# RYDAPLink.net
KiCad netlist of a schematic drawn in EasyEDA Pro
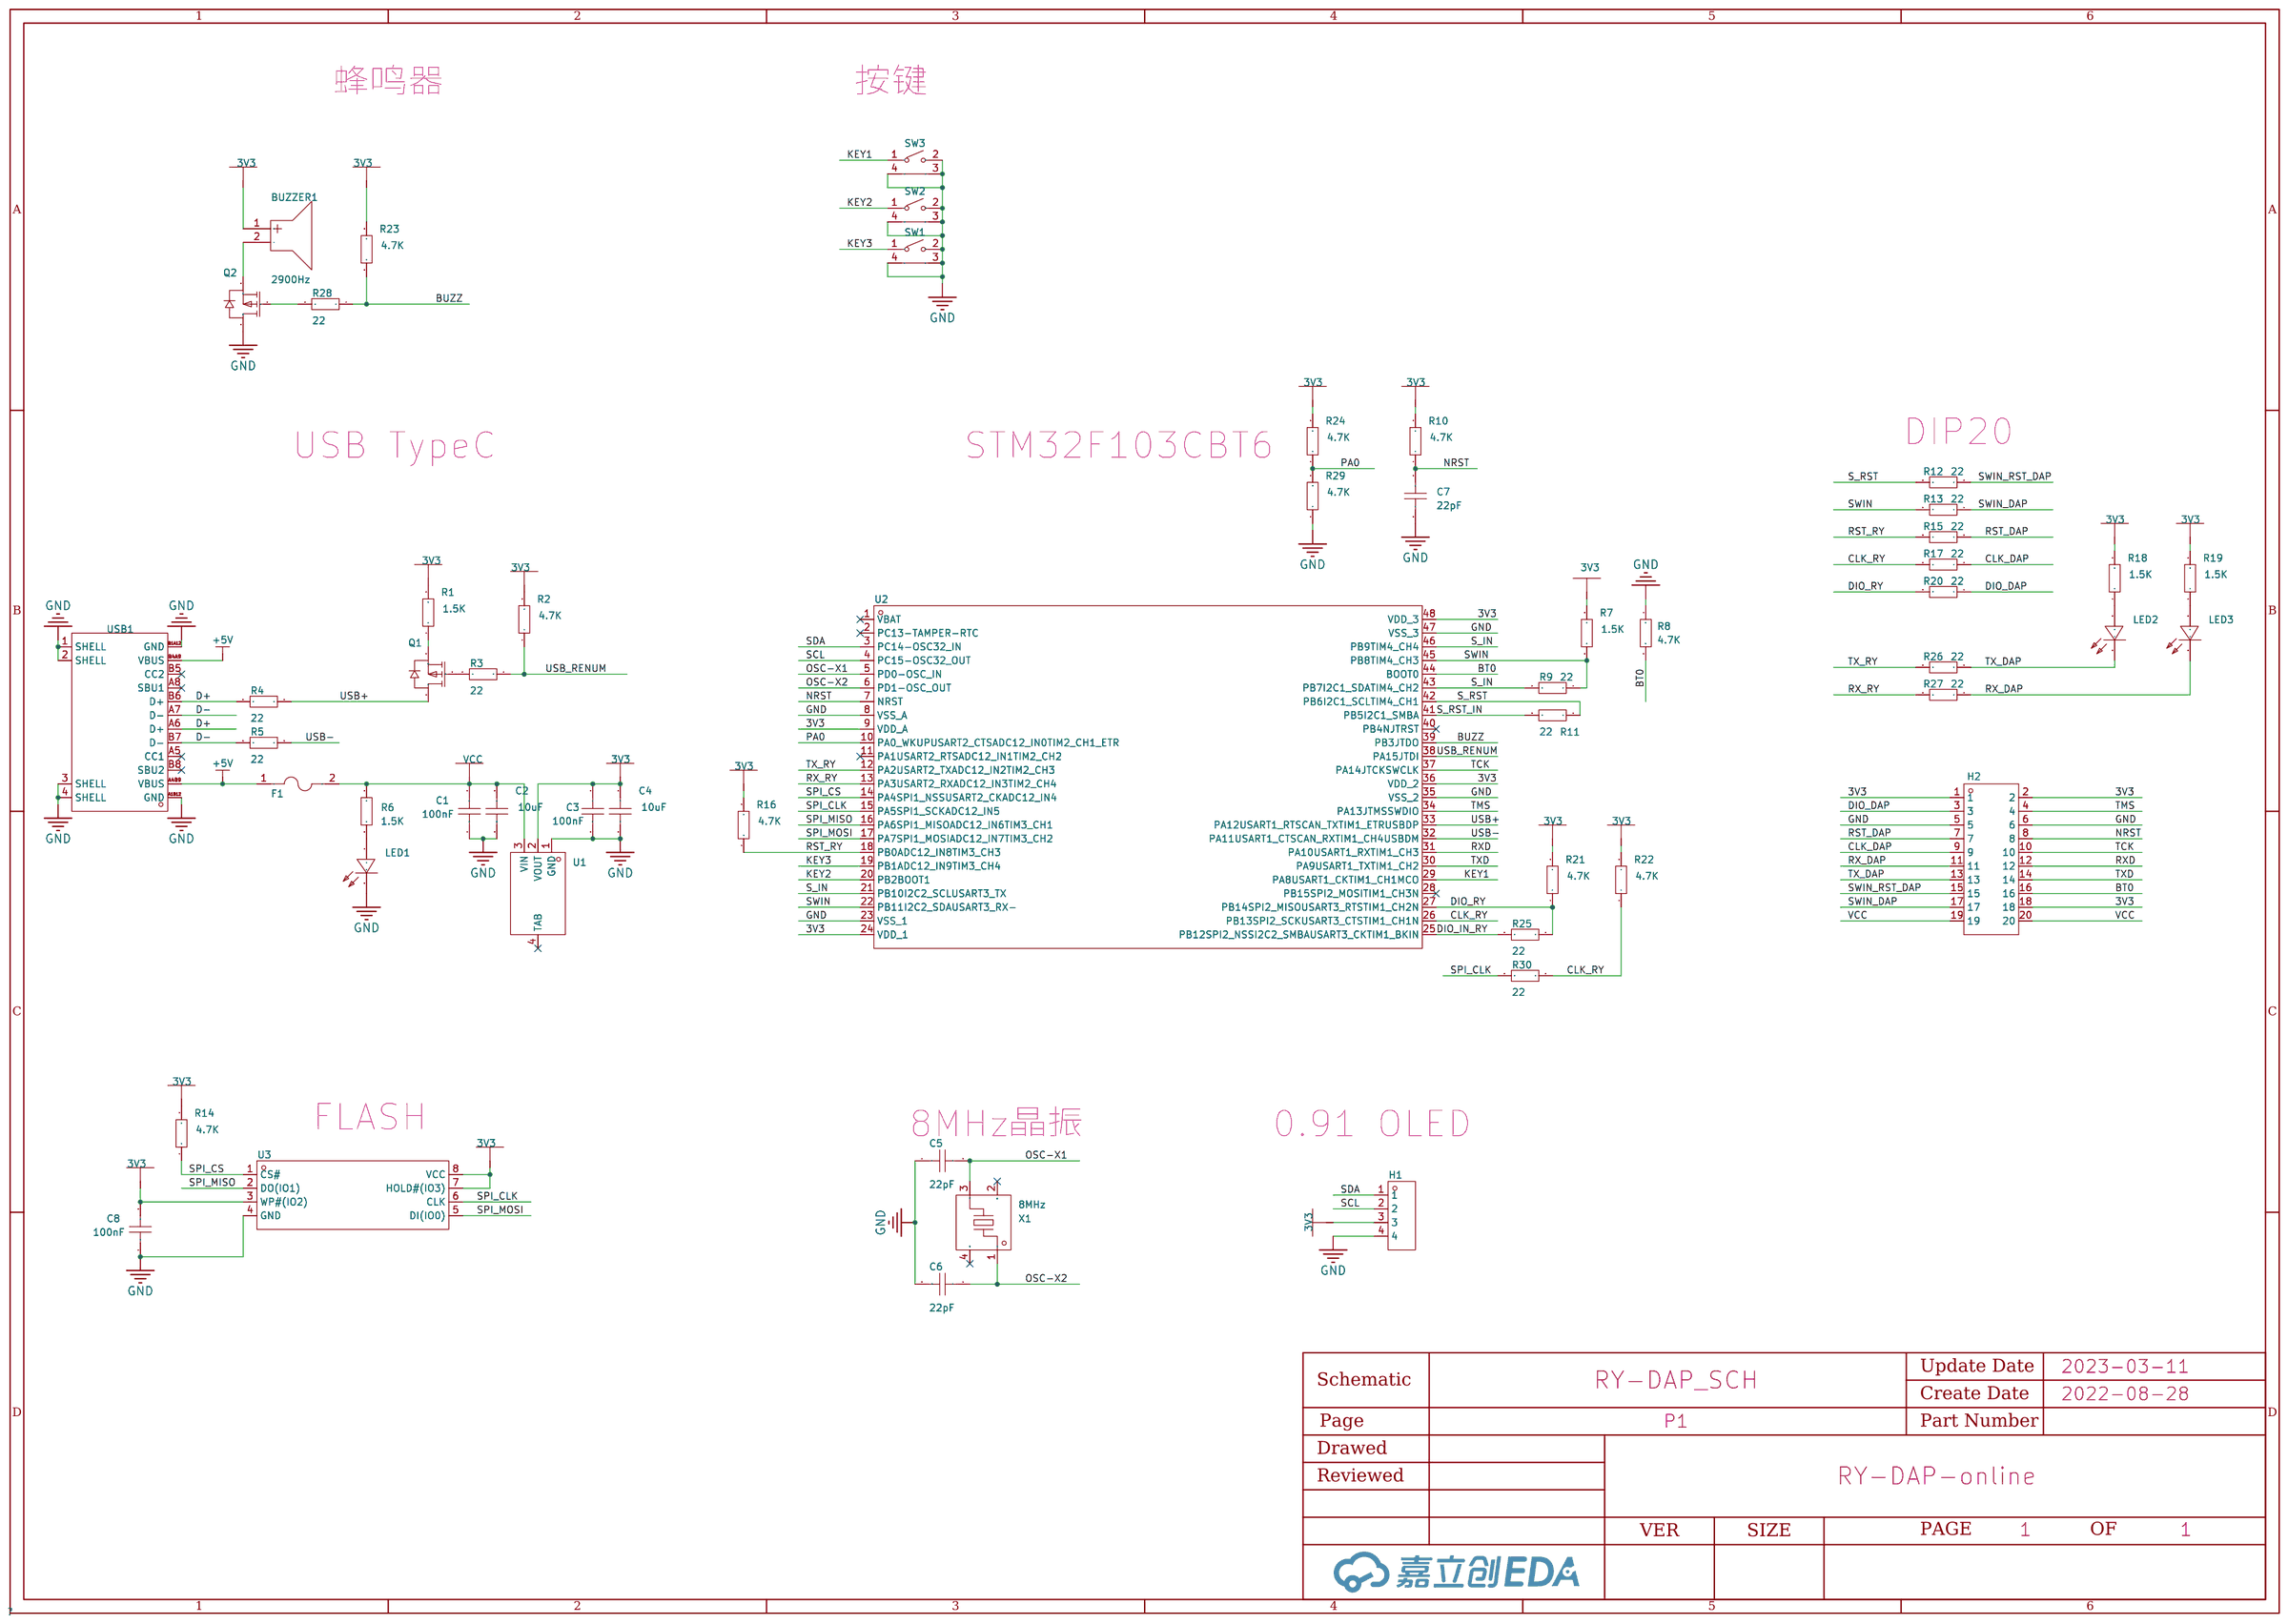
[diagram p0: schematic sheet]

(export (version "E")
  (design (tool "Eeschema 10.0.6"))
  (components
    (comp (ref "BUZZER1")
      (value "2900Hz")
      (footprint "easyedapro:BUZ-TH_BD9.6-P5.00-D0.7-FD")
      (description "驱动方式:有源(内含驱动线路);构造类型:电磁式;额定电压:3V;工作电压:2V~4V;频率:2900Hz;声压(SPL):85dB@3V,10cm;直径(φD):9.6mm;高度:5.2mm;")
      (fields (field (name "Manufacturer Part") "Cy-9650-3029") (field (name "Manufacturer") "CY(超音)"))
      (libsource (lib "easyedapro") (part "CY-9650-3029"))
    )
    (comp (ref "C1")
      (value "100nF")
      (footprint "easyedapro:C0603")
      (description "容值:100nF;精度:±10%;额定电压:50V;温度系数:X7R;")
      (fields
        (field (name "Manufacturer Part") "CC0603KRX7R9BB104")
        (field (name "Manufacturer") "YAGEO(国巨)")
      )
      (libsource (lib "easyedapro") (part "CC0603KRX7R9BB104"))
    )
    (comp (ref "C2")
      (value "10uF")
      (footprint "easyedapro:C0603")
      (description "容值:33pF;精度:±1%;额定电压:50V;温度系数:NP0;")
      (fields
        (field (name "Manufacturer Part") "CC0805FRNPO9BN330")
        (field (name "Manufacturer") "YAGEO(国巨)")
      )
      (libsource (lib "easyedapro") (part "CC0805FRNPO9BN330"))
    )
    (comp (ref "C3")
      (value "100nF")
      (footprint "easyedapro:C0603")
      (description "容值:100nF;精度:±10%;额定电压:50V;温度系数:X7R;")
      (fields
        (field (name "Manufacturer Part") "CC0603KRX7R9BB104")
        (field (name "Manufacturer") "YAGEO(国巨)")
      )
      (libsource (lib "easyedapro") (part "CC0603KRX7R9BB104"))
    )
    (comp (ref "C4")
      (value "10uF")
      (footprint "easyedapro:C0603")
      (description "容值:33pF;精度:±1%;额定电压:50V;温度系数:NP0;")
      (fields
        (field (name "Manufacturer Part") "CC0805FRNPO9BN330")
        (field (name "Manufacturer") "YAGEO(国巨)")
      )
      (libsource (lib "easyedapro") (part "CC0805FRNPO9BN330"))
    )
    (comp (ref "C5")
      (value "22pF")
      (footprint "easyedapro:C0603")
      (description "容值:33pF;精度:±1%;额定电压:50V;温度系数:NP0;")
      (fields
        (field (name "Manufacturer Part") "CC0805FRNPO9BN330")
        (field (name "Manufacturer") "YAGEO(国巨)")
      )
      (libsource (lib "easyedapro") (part "CC0805FRNPO9BN330"))
    )
    (comp (ref "C6")
      (value "22pF")
      (footprint "easyedapro:C0603")
      (description "容值:33pF;精度:±1%;额定电压:50V;温度系数:NP0;")
      (fields
        (field (name "Manufacturer Part") "CC0805FRNPO9BN330")
        (field (name "Manufacturer") "YAGEO(国巨)")
      )
      (libsource (lib "easyedapro") (part "CC0805FRNPO9BN330"))
    )
    (comp (ref "C7")
      (value "22pF")
      (footprint "easyedapro:C0603")
      (description "容值:33pF;精度:±1%;额定电压:50V;温度系数:NP0;")
      (fields
        (field (name "Manufacturer Part") "CC0805FRNPO9BN330")
        (field (name "Manufacturer") "YAGEO(国巨)")
      )
      (libsource (lib "easyedapro") (part "CC0805FRNPO9BN330"))
    )
    (comp (ref "C8")
      (value "100nF")
      (footprint "easyedapro:C0603")
      (description "容值:100nF;精度:±10%;额定电压:50V;温度系数:X7R;")
      (fields
        (field (name "Manufacturer Part") "CC0603KRX7R9BB104")
        (field (name "Manufacturer") "YAGEO(国巨)")
      )
      (libsource (lib "easyedapro") (part "CC0603KRX7R9BB104"))
    )
    (comp (ref "F1")
      (value "~")
      (footprint "easyedapro:F0805")
      (fields (field (name "Manufacturer Part") "ASMD0805-075") (field (name "Manufacturer") "JDTfuse集电通"))
      (libsource (lib "easyedapro") (part "ASMD0805-075"))
    )
    (comp (ref "H1")
      (value "~")
      (footprint "easyedapro:HDR-TH_4P-P2.54-V-M")
      (fields
        (field (name "Manufacturer Part") "KH-2.54PH180-1X4P-L11.5")
        (field (name "Manufacturer") "kinghelm(金航标)")
      )
      (libsource (lib "easyedapro") (part "KH-2.54PH180-1X4P-L11.5"))
    )
    (comp (ref "H2")
      (value "~")
      (footprint "easyedapro:HDR-TH_20P-P2.54-V-M-R2-C10-S2.54")
      (fields
        (field (name "Manufacturer Part") "1125-1210G0S120C002")
        (field (name "Manufacturer") "Wcon(维峰电子)")
      )
      (libsource (lib "easyedapro") (part "1125-1210G0S120C002"))
    )
    (comp (ref "LED1")
      (value "~")
      (footprint "easyedapro:LED0603-R-RD_RED")
      (description "尺寸1.6x0.8x0.8；IF=20ma：1.6~2.6v，620~640nm,51~150mcd金线，光强高，功耗低，可靠性好，寿命长")
      (fields (field (name "Manufacturer Part") "NCD0603R3") (field (name "Manufacturer") "国星光电"))
      (libsource (lib "easyedapro") (part "NCD0603R3"))
    )
    (comp (ref "LED2")
      (value "~")
      (footprint "easyedapro:LED0603-R-RD_RED")
      (description "尺寸1.6x0.8x0.8；IF=20ma：1.6~2.6v，620~640nm,51~150mcd金线，光强高，功耗低，可靠性好，寿命长")
      (fields (field (name "Manufacturer Part") "NCD0603R3") (field (name "Manufacturer") "国星光电"))
      (libsource (lib "easyedapro") (part "NCD0603R3"))
    )
    (comp (ref "LED3")
      (value "~")
      (footprint "easyedapro:LED0603-R-RD_RED")
      (description "尺寸1.6x0.8x0.8；IF=20ma：1.6~2.6v，620~640nm,51~150mcd金线，光强高，功耗低，可靠性好，寿命长")
      (fields (field (name "Manufacturer Part") "NCD0603R3") (field (name "Manufacturer") "国星光电"))
      (libsource (lib "easyedapro") (part "NCD0603R3"))
    )
    (comp (ref "Q1")
      (value "~")
      (footprint "easyedapro:SOT-23-3_L2.9-W1.4-P1.90-LS2.6-BR")
      (fields (field (name "Manufacturer Part") "AO3401") (field (name "Manufacturer") "TWGMC(台湾迪嘉)"))
      (libsource (lib "easyedapro") (part "AO3401_C727156"))
    )
    (comp (ref "Q2")
      (value "~")
      (footprint "easyedapro:SOT-23-3_L2.9-W1.4-P1.90-LS2.6-BR")
      (fields (field (name "Manufacturer Part") "AO3401") (field (name "Manufacturer") "TWGMC(台湾迪嘉)"))
      (libsource (lib "easyedapro") (part "AO3401_C727156"))
    )
    (comp (ref "R1")
      (value "1.5K")
      (footprint "easyedapro:R0603")
      (description "电阻类型:薄膜电阻;阻值:10kΩ;精度:±0.1%;功率:100mW;温度系数:±25ppm/;最大工作电压:75V;工作温度范围:-55~+155;")
      (fields
        (field (name "Manufacturer Part") "TR0603B10K0P0525Z")
        (field (name "Manufacturer") "EVER OHMS(天二科技)")
      )
      (libsource (lib "easyedapro") (part "R_0603_EU"))
    )
    (comp (ref "R2")
      (value "4.7K")
      (footprint "easyedapro:R0603")
      (description "电阻类型:薄膜电阻;阻值:10kΩ;精度:±0.1%;功率:100mW;温度系数:±25ppm/;最大工作电压:75V;工作温度范围:-55~+155;")
      (fields
        (field (name "Manufacturer Part") "TR0603B10K0P0525Z")
        (field (name "Manufacturer") "EVER OHMS(天二科技)")
      )
      (libsource (lib "easyedapro") (part "R_0603_EU"))
    )
    (comp (ref "R3")
      (value "22")
      (footprint "easyedapro:R0603")
      (description "电阻类型:薄膜电阻;阻值:10kΩ;精度:±0.1%;功率:100mW;温度系数:±25ppm/;最大工作电压:75V;工作温度范围:-55~+155;")
      (fields
        (field (name "Manufacturer Part") "TR0603B10K0P0525Z")
        (field (name "Manufacturer") "EVER OHMS(天二科技)")
      )
      (libsource (lib "easyedapro") (part "R_0603_EU"))
    )
    (comp (ref "R4")
      (value "22")
      (footprint "easyedapro:R0603")
      (description "电阻类型:薄膜电阻;阻值:10kΩ;精度:±0.1%;功率:100mW;温度系数:±25ppm/;最大工作电压:75V;工作温度范围:-55~+155;")
      (fields
        (field (name "Manufacturer Part") "TR0603B10K0P0525Z")
        (field (name "Manufacturer") "EVER OHMS(天二科技)")
      )
      (libsource (lib "easyedapro") (part "R_0603_EU"))
    )
    (comp (ref "R5")
      (value "22")
      (footprint "easyedapro:R0603")
      (description "电阻类型:薄膜电阻;阻值:10kΩ;精度:±0.1%;功率:100mW;温度系数:±25ppm/;最大工作电压:75V;工作温度范围:-55~+155;")
      (fields
        (field (name "Manufacturer Part") "TR0603B10K0P0525Z")
        (field (name "Manufacturer") "EVER OHMS(天二科技)")
      )
      (libsource (lib "easyedapro") (part "R_0603_EU"))
    )
    (comp (ref "R6")
      (value "1.5K")
      (footprint "easyedapro:R0603")
      (description "电阻类型:薄膜电阻;阻值:10kΩ;精度:±0.1%;功率:100mW;温度系数:±25ppm/;最大工作电压:75V;工作温度范围:-55~+155;")
      (fields
        (field (name "Manufacturer Part") "TR0603B10K0P0525Z")
        (field (name "Manufacturer") "EVER OHMS(天二科技)")
      )
      (libsource (lib "easyedapro") (part "R_0603_EU"))
    )
    (comp (ref "R7")
      (value "1.5K")
      (footprint "easyedapro:R0603")
      (description "电阻类型:薄膜电阻;阻值:10kΩ;精度:±0.1%;功率:100mW;温度系数:±25ppm/;最大工作电压:75V;工作温度范围:-55~+155;")
      (fields
        (field (name "Manufacturer Part") "TR0603B10K0P0525Z")
        (field (name "Manufacturer") "EVER OHMS(天二科技)")
      )
      (libsource (lib "easyedapro") (part "R_0603_EU"))
    )
    (comp (ref "R8")
      (value "4.7K")
      (footprint "easyedapro:R0603")
      (description "电阻类型:薄膜电阻;阻值:10kΩ;精度:±0.1%;功率:100mW;温度系数:±25ppm/;最大工作电压:75V;工作温度范围:-55~+155;")
      (fields
        (field (name "Manufacturer Part") "TR0603B10K0P0525Z")
        (field (name "Manufacturer") "EVER OHMS(天二科技)")
      )
      (libsource (lib "easyedapro") (part "R_0603_EU"))
    )
    (comp (ref "R9")
      (value "22")
      (footprint "easyedapro:R0603")
      (description "电阻类型:薄膜电阻;阻值:10kΩ;精度:±0.1%;功率:100mW;温度系数:±25ppm/;最大工作电压:75V;工作温度范围:-55~+155;")
      (fields
        (field (name "Manufacturer Part") "TR0603B10K0P0525Z")
        (field (name "Manufacturer") "EVER OHMS(天二科技)")
      )
      (libsource (lib "easyedapro") (part "R_0603_EU"))
    )
    (comp (ref "R10")
      (value "4.7K")
      (footprint "easyedapro:R0603")
      (description "电阻类型:薄膜电阻;阻值:10kΩ;精度:±0.1%;功率:100mW;温度系数:±25ppm/;最大工作电压:75V;工作温度范围:-55~+155;")
      (fields
        (field (name "Manufacturer Part") "TR0603B10K0P0525Z")
        (field (name "Manufacturer") "EVER OHMS(天二科技)")
      )
      (libsource (lib "easyedapro") (part "R_0603_EU"))
    )
    (comp (ref "R11")
      (value "22")
      (footprint "easyedapro:R0603")
      (description "电阻类型:薄膜电阻;阻值:10kΩ;精度:±0.1%;功率:100mW;温度系数:±25ppm/;最大工作电压:75V;工作温度范围:-55~+155;")
      (fields
        (field (name "Manufacturer Part") "TR0603B10K0P0525Z")
        (field (name "Manufacturer") "EVER OHMS(天二科技)")
      )
      (libsource (lib "easyedapro") (part "R_0603_EU"))
    )
    (comp (ref "R12")
      (value "22")
      (footprint "easyedapro:R0603")
      (description "电阻类型:薄膜电阻;阻值:10kΩ;精度:±0.1%;功率:100mW;温度系数:±25ppm/;最大工作电压:75V;工作温度范围:-55~+155;")
      (fields
        (field (name "Manufacturer Part") "TR0603B10K0P0525Z")
        (field (name "Manufacturer") "EVER OHMS(天二科技)")
      )
      (libsource (lib "easyedapro") (part "R_0603_EU"))
    )
    (comp (ref "R13")
      (value "22")
      (footprint "easyedapro:R0603")
      (description "电阻类型:薄膜电阻;阻值:10kΩ;精度:±0.1%;功率:100mW;温度系数:±25ppm/;最大工作电压:75V;工作温度范围:-55~+155;")
      (fields
        (field (name "Manufacturer Part") "TR0603B10K0P0525Z")
        (field (name "Manufacturer") "EVER OHMS(天二科技)")
      )
      (libsource (lib "easyedapro") (part "R_0603_EU"))
    )
    (comp (ref "R14")
      (value "4.7K")
      (footprint "easyedapro:R0603")
      (description "电阻类型:薄膜电阻;阻值:10kΩ;精度:±0.1%;功率:100mW;温度系数:±25ppm/;最大工作电压:75V;工作温度范围:-55~+155;")
      (fields
        (field (name "Manufacturer Part") "TR0603B10K0P0525Z")
        (field (name "Manufacturer") "EVER OHMS(天二科技)")
      )
      (libsource (lib "easyedapro") (part "R_0603_EU"))
    )
    (comp (ref "R15")
      (value "22")
      (footprint "easyedapro:R0603")
      (description "电阻类型:薄膜电阻;阻值:10kΩ;精度:±0.1%;功率:100mW;温度系数:±25ppm/;最大工作电压:75V;工作温度范围:-55~+155;")
      (fields
        (field (name "Manufacturer Part") "TR0603B10K0P0525Z")
        (field (name "Manufacturer") "EVER OHMS(天二科技)")
      )
      (libsource (lib "easyedapro") (part "R_0603_EU"))
    )
    (comp (ref "R16")
      (value "4.7K")
      (footprint "easyedapro:R0603")
      (description "电阻类型:薄膜电阻;阻值:10kΩ;精度:±0.1%;功率:100mW;温度系数:±25ppm/;最大工作电压:75V;工作温度范围:-55~+155;")
      (fields
        (field (name "Manufacturer Part") "TR0603B10K0P0525Z")
        (field (name "Manufacturer") "EVER OHMS(天二科技)")
      )
      (libsource (lib "easyedapro") (part "R_0603_EU"))
    )
    (comp (ref "R17")
      (value "22")
      (footprint "easyedapro:R0603")
      (description "电阻类型:薄膜电阻;阻值:10kΩ;精度:±0.1%;功率:100mW;温度系数:±25ppm/;最大工作电压:75V;工作温度范围:-55~+155;")
      (fields
        (field (name "Manufacturer Part") "TR0603B10K0P0525Z")
        (field (name "Manufacturer") "EVER OHMS(天二科技)")
      )
      (libsource (lib "easyedapro") (part "R_0603_EU"))
    )
    (comp (ref "R18")
      (value "1.5K")
      (footprint "easyedapro:R0603")
      (description "电阻类型:薄膜电阻;阻值:10kΩ;精度:±0.1%;功率:100mW;温度系数:±25ppm/;最大工作电压:75V;工作温度范围:-55~+155;")
      (fields
        (field (name "Manufacturer Part") "TR0603B10K0P0525Z")
        (field (name "Manufacturer") "EVER OHMS(天二科技)")
      )
      (libsource (lib "easyedapro") (part "R_0603_EU"))
    )
    (comp (ref "R19")
      (value "1.5K")
      (footprint "easyedapro:R0603")
      (description "电阻类型:薄膜电阻;阻值:10kΩ;精度:±0.1%;功率:100mW;温度系数:±25ppm/;最大工作电压:75V;工作温度范围:-55~+155;")
      (fields
        (field (name "Manufacturer Part") "TR0603B10K0P0525Z")
        (field (name "Manufacturer") "EVER OHMS(天二科技)")
      )
      (libsource (lib "easyedapro") (part "R_0603_EU"))
    )
    (comp (ref "R20")
      (value "22")
      (footprint "easyedapro:R0603")
      (description "电阻类型:薄膜电阻;阻值:10kΩ;精度:±0.1%;功率:100mW;温度系数:±25ppm/;最大工作电压:75V;工作温度范围:-55~+155;")
      (fields
        (field (name "Manufacturer Part") "TR0603B10K0P0525Z")
        (field (name "Manufacturer") "EVER OHMS(天二科技)")
      )
      (libsource (lib "easyedapro") (part "R_0603_EU"))
    )
    (comp (ref "R21")
      (value "4.7K")
      (footprint "easyedapro:R0603")
      (description "电阻类型:薄膜电阻;阻值:10kΩ;精度:±0.1%;功率:100mW;温度系数:±25ppm/;最大工作电压:75V;工作温度范围:-55~+155;")
      (fields
        (field (name "Manufacturer Part") "TR0603B10K0P0525Z")
        (field (name "Manufacturer") "EVER OHMS(天二科技)")
      )
      (libsource (lib "easyedapro") (part "R_0603_EU"))
    )
    (comp (ref "R22")
      (value "4.7K")
      (footprint "easyedapro:R0603")
      (description "电阻类型:薄膜电阻;阻值:10kΩ;精度:±0.1%;功率:100mW;温度系数:±25ppm/;最大工作电压:75V;工作温度范围:-55~+155;")
      (fields
        (field (name "Manufacturer Part") "TR0603B10K0P0525Z")
        (field (name "Manufacturer") "EVER OHMS(天二科技)")
      )
      (libsource (lib "easyedapro") (part "R_0603_EU"))
    )
    (comp (ref "R23")
      (value "4.7K")
      (footprint "easyedapro:R0603")
      (description "电阻类型:薄膜电阻;阻值:10kΩ;精度:±0.1%;功率:100mW;温度系数:±25ppm/;最大工作电压:75V;工作温度范围:-55~+155;")
      (fields
        (field (name "Manufacturer Part") "TR0603B10K0P0525Z")
        (field (name "Manufacturer") "EVER OHMS(天二科技)")
      )
      (libsource (lib "easyedapro") (part "R_0603_EU"))
    )
    (comp (ref "R24")
      (value "4.7K")
      (footprint "easyedapro:R0603")
      (description "电阻类型:薄膜电阻;阻值:10kΩ;精度:±0.1%;功率:100mW;温度系数:±25ppm/;最大工作电压:75V;工作温度范围:-55~+155;")
      (fields
        (field (name "Manufacturer Part") "TR0603B10K0P0525Z")
        (field (name "Manufacturer") "EVER OHMS(天二科技)")
      )
      (libsource (lib "easyedapro") (part "R_0603_EU"))
    )
    (comp (ref "R25")
      (value "22")
      (footprint "easyedapro:R0603")
      (description "电阻类型:薄膜电阻;阻值:10kΩ;精度:±0.1%;功率:100mW;温度系数:±25ppm/;最大工作电压:75V;工作温度范围:-55~+155;")
      (fields
        (field (name "Manufacturer Part") "TR0603B10K0P0525Z")
        (field (name "Manufacturer") "EVER OHMS(天二科技)")
      )
      (libsource (lib "easyedapro") (part "R_0603_EU"))
    )
    (comp (ref "R26")
      (value "22")
      (footprint "easyedapro:R0603")
      (description "电阻类型:薄膜电阻;阻值:10kΩ;精度:±0.1%;功率:100mW;温度系数:±25ppm/;最大工作电压:75V;工作温度范围:-55~+155;")
      (fields
        (field (name "Manufacturer Part") "TR0603B10K0P0525Z")
        (field (name "Manufacturer") "EVER OHMS(天二科技)")
      )
      (libsource (lib "easyedapro") (part "R_0603_EU"))
    )
    (comp (ref "R27")
      (value "22")
      (footprint "easyedapro:R0603")
      (description "电阻类型:薄膜电阻;阻值:10kΩ;精度:±0.1%;功率:100mW;温度系数:±25ppm/;最大工作电压:75V;工作温度范围:-55~+155;")
      (fields
        (field (name "Manufacturer Part") "TR0603B10K0P0525Z")
        (field (name "Manufacturer") "EVER OHMS(天二科技)")
      )
      (libsource (lib "easyedapro") (part "R_0603_EU"))
    )
    (comp (ref "R28")
      (value "22")
      (footprint "easyedapro:R0603")
      (description "电阻类型:薄膜电阻;阻值:10kΩ;精度:±0.1%;功率:100mW;温度系数:±25ppm/;最大工作电压:75V;工作温度范围:-55~+155;")
      (fields
        (field (name "Manufacturer Part") "TR0603B10K0P0525Z")
        (field (name "Manufacturer") "EVER OHMS(天二科技)")
      )
      (libsource (lib "easyedapro") (part "R_0603_EU"))
    )
    (comp (ref "R29")
      (value "4.7K")
      (footprint "easyedapro:R0603")
      (description "电阻类型:薄膜电阻;阻值:10kΩ;精度:±0.1%;功率:100mW;温度系数:±25ppm/;最大工作电压:75V;工作温度范围:-55~+155;")
      (fields
        (field (name "Manufacturer Part") "TR0603B10K0P0525Z")
        (field (name "Manufacturer") "EVER OHMS(天二科技)")
      )
      (libsource (lib "easyedapro") (part "R_0603_EU"))
    )
    (comp (ref "R30")
      (value "22")
      (footprint "easyedapro:R0603")
      (description "电阻类型:薄膜电阻;阻值:10kΩ;精度:±0.1%;功率:100mW;温度系数:±25ppm/;最大工作电压:75V;工作温度范围:-55~+155;")
      (fields
        (field (name "Manufacturer Part") "TR0603B10K0P0525Z")
        (field (name "Manufacturer") "EVER OHMS(天二科技)")
      )
      (libsource (lib "easyedapro") (part "R_0603_EU"))
    )
    (comp (ref "SW1")
      (value "~")
      (footprint "easyedapro:SW-SMD_TS-1012A-AC05026")
      (fields (field (name "Manufacturer Part") "TS-1012A-AC05026") (field (name "Manufacturer") "XUNPU(讯普)"))
      (libsource (lib "easyedapro") (part "TS-1012A-AC05026"))
    )
    (comp (ref "SW2")
      (value "~")
      (footprint "easyedapro:SW-SMD_TS-1012A-AC05026")
      (fields (field (name "Manufacturer Part") "TS-1012A-AC05026") (field (name "Manufacturer") "XUNPU(讯普)"))
      (libsource (lib "easyedapro") (part "TS-1012A-AC05026"))
    )
    (comp (ref "SW3")
      (value "~")
      (footprint "easyedapro:SW-SMD_TS-1012A-AC05026")
      (fields (field (name "Manufacturer Part") "TS-1012A-AC05026") (field (name "Manufacturer") "XUNPU(讯普)"))
      (libsource (lib "easyedapro") (part "TS-1012A-AC05026"))
    )
    (comp (ref "U1")
      (value "~")
      (footprint "easyedapro:SOT-223-3_L6.5-W3.4-P2.30-LS7.0-BR")
      (description "输出类型:固定;输出极性:正;输出通道数:1;最大输入电压:18V;输出电压:3.3V;压差:1.4V@(1A);输出电流:800mA;电源纹波抑制比(PRSS):-;")
      (fields (field (name "Manufacturer Part") "AMS1117-3.3") (field (name "Manufacturer") "PUOLOP(迪浦)"))
      (libsource (lib "easyedapro") (part "AMS1117-3.3_C351784"))
    )
    (comp (ref "U2")
      (value "~")
      (footprint "easyedapro:LQFP-48_L7.0-W7.0-P0.50-LS9.0-BL")
      (description "主频（MAX):72MHz;工作电压:2V ~ 3.6V;")
      (fields (field (name "Manufacturer Part") "STM32F103CBT6") (field (name "Manufacturer") "ST(意法半导体)"))
      (libsource (lib "easyedapro") (part "STM32F103CBT6"))
    )
    (comp (ref "U3")
      (value "~")
      (footprint "easyedapro:SOIC-8_L5.3-W5.3-P1.27-LS8.0-BL")
      (fields (field (name "Manufacturer Part") "W25Q64FVSSIQ") (field (name "Manufacturer") "WINBOND(华邦)"))
      (libsource (lib "easyedapro") (part "W25Q64FVSSIQ"))
    )
    (comp (ref "USB1")
      (value "~")
      (footprint "easyedapro:USB-C-SMD_G-SWITCH_GT-USB-7010EN")
      (description "连接器类型:Type-C;公母:母座;触点数量:16;端口数量:1;安装方式:卧贴;")
      (fields
        (field (name "Manufacturer Part") "HC-TYPE-C-16P-01A-R")
        (field (name "Manufacturer") "HCTL(华灿天禄)")
      )
      (libsource (lib "easyedapro") (part "HC-TYPE-C-16P-01A-R"))
    )
    (comp (ref "X1")
      (value "8MHz")
      (footprint "easyedapro:CRYSTAL-SMD_4P-L3.2-W2.5-BL")
      (description "晶振类型:-;频率:-;频率公差:-;频率稳定度:-;负载电容:-;工作温度:-;")
      (fields (field (name "Manufacturer Part") "C3SB8.000F20E12") (field (name "Manufacturer") "川晶科技"))
      (libsource (lib "easyedapro") (part "C3SB8.000F20E12"))
    )
  )
  (nets
    (net (code "1") (name "+5V") (class "Default")
      (node (ref "F1") (pin "1") (pinfunction "1_1") (pintype "input"))
      (node (ref "USB1") (pin "A4B9") (pinfunction "VBUS_A4B9") (pintype "input"))
      (node (ref "USB1") (pin "B4A9") (pinfunction "VBUS_B4A9") (pintype "input"))
    )
    (net (code "2") (name "/BT0") (class "Default")
      (node (ref "H2") (pin "16") (pinfunction "16_16") (pintype "input"))
      (node (ref "R8") (pin "2") (pinfunction "2_2") (pintype "input"))
      (node (ref "U2") (pin "44") (pinfunction "BOOT0_44") (pintype "input"))
    )
    (net (code "3") (name "/BUZZ") (class "Default")
      (node (ref "R23") (pin "1") (pinfunction "1_1") (pintype "input"))
      (node (ref "R28") (pin "1") (pinfunction "1_1") (pintype "input"))
      (node (ref "U2") (pin "39") (pinfunction "PB3JTDO_39") (pintype "input"))
    )
    (net (code "4") (name "/CLK_DAP") (class "Default")
      (node (ref "H2") (pin "9") (pinfunction "9_9") (pintype "input"))
      (node (ref "R17") (pin "1") (pinfunction "1_1") (pintype "input"))
    )
    (net (code "5") (name "/CLK_RY") (class "Default")
      (node (ref "R17") (pin "2") (pinfunction "2_2") (pintype "input"))
      (node (ref "R22") (pin "1") (pinfunction "1_1") (pintype "input"))
      (node (ref "R30") (pin "1") (pinfunction "1_1") (pintype "input"))
      (node (ref "U2") (pin "26") (pinfunction "PB13SPI2_SCKUSART3_CTSTIM1_CH1N_26") (pintype "input"))
    )
    (net (code "6") (name "/D+") (class "Default")
      (node (ref "R4") (pin "2") (pinfunction "2_2") (pintype "input"))
      (node (ref "USB1") (pin "A6") (pinfunction "D+_A6") (pintype "input"))
      (node (ref "USB1") (pin "B6") (pinfunction "D+_B6") (pintype "input"))
    )
    (net (code "7") (name "/D-") (class "Default")
      (node (ref "R5") (pin "2") (pinfunction "2_2") (pintype "input"))
      (node (ref "USB1") (pin "A7") (pinfunction "D-_A7") (pintype "input"))
      (node (ref "USB1") (pin "B7") (pinfunction "D-_B7") (pintype "input"))
    )
    (net (code "8") (name "/DIO_DAP") (class "Default")
      (node (ref "H2") (pin "3") (pinfunction "3_3") (pintype "input"))
      (node (ref "R20") (pin "1") (pinfunction "1_1") (pintype "input"))
    )
    (net (code "9") (name "/DIO_IN_RY") (class "Default")
      (node (ref "R25") (pin "2") (pinfunction "2_2") (pintype "input"))
      (node (ref "U2") (pin "25") (pinfunction "PB12SPI2_NSSI2C2_SMBAUSART3_CKTIM1_BKIN_25") (pintype "input"))
    )
    (net (code "10") (name "/DIO_RY") (class "Default")
      (node (ref "R20") (pin "2") (pinfunction "2_2") (pintype "input"))
      (node (ref "R21") (pin "1") (pinfunction "1_1") (pintype "input"))
      (node (ref "R25") (pin "1") (pinfunction "1_1") (pintype "input"))
      (node (ref "U2") (pin "27") (pinfunction "PB14SPI2_MISOUSART3_RTSTIM1_CH2N_27") (pintype "input"))
    )
    (net (code "11") (name "/KEY1") (class "Default")
      (node (ref "SW3") (pin "1") (pinfunction "1_1") (pintype "input"))
      (node (ref "U2") (pin "29") (pinfunction "PA8USART1_CKTIM1_CH1MCO_29") (pintype "input"))
    )
    (net (code "12") (name "/KEY2") (class "Default")
      (node (ref "SW2") (pin "1") (pinfunction "1_1") (pintype "input"))
      (node (ref "U2") (pin "20") (pinfunction "PB2BOOT1_20") (pintype "input"))
    )
    (net (code "13") (name "/KEY3") (class "Default")
      (node (ref "SW1") (pin "1") (pinfunction "1_1") (pintype "input"))
      (node (ref "U2") (pin "19") (pinfunction "PB1ADC12_IN9TIM3_CH4_19") (pintype "input"))
    )
    (net (code "14") (name "/NRST") (class "Default")
      (node (ref "C7") (pin "1") (pinfunction "1_1") (pintype "input"))
      (node (ref "H2") (pin "8") (pinfunction "8_8") (pintype "input"))
      (node (ref "R10") (pin "1") (pinfunction "1_1") (pintype "input"))
      (node (ref "U2") (pin "7") (pinfunction "NRST_7") (pintype "input"))
    )
    (net (code "15") (name "/OSC-X1") (class "Default")
      (node (ref "C5") (pin "2") (pinfunction "2_2") (pintype "input"))
      (node (ref "U2") (pin "5") (pinfunction "PD0-OSC_IN_5") (pintype "input"))
      (node (ref "X1") (pin "3") (pinfunction "3_3") (pintype "input"))
    )
    (net (code "16") (name "/OSC-X2") (class "Default")
      (node (ref "C6") (pin "1") (pinfunction "1_1") (pintype "input"))
      (node (ref "U2") (pin "6") (pinfunction "PD1-OSC_OUT_6") (pintype "input"))
      (node (ref "X1") (pin "1") (pinfunction "1_1") (pintype "input"))
    )
    (net (code "17") (name "/PA0") (class "Default")
      (node (ref "R24") (pin "1") (pinfunction "1_1") (pintype "input"))
      (node (ref "R29") (pin "2") (pinfunction "2_2") (pintype "input"))
      (node (ref "U2") (pin "10") (pinfunction "PA0_WKUPUSART2_CTSADC12_IN0TIM2_CH1_ETR_10") (pintype "input"))
    )
    (net (code "18") (name "/RST_DAP") (class "Default")
      (node (ref "H2") (pin "7") (pinfunction "7_7") (pintype "input"))
      (node (ref "R15") (pin "1") (pinfunction "1_1") (pintype "input"))
    )
    (net (code "19") (name "/RST_RY") (class "Default")
      (node (ref "R15") (pin "2") (pinfunction "2_2") (pintype "input"))
      (node (ref "R16") (pin "1") (pinfunction "1_1") (pintype "input"))
      (node (ref "U2") (pin "18") (pinfunction "PB0ADC12_IN8TIM3_CH3_18") (pintype "input"))
    )
    (net (code "20") (name "/RXD") (class "Default")
      (node (ref "H2") (pin "12") (pinfunction "12_12") (pintype "input"))
      (node (ref "U2") (pin "31") (pinfunction "PA10USART1_RXTIM1_CH3_31") (pintype "input"))
    )
    (net (code "21") (name "/RX_DAP") (class "Default")
      (node (ref "H2") (pin "11") (pinfunction "11_11") (pintype "input"))
      (node (ref "LED3") (pin "2") (pinfunction "K_2") (pintype "input"))
      (node (ref "R27") (pin "1") (pinfunction "1_1") (pintype "input"))
    )
    (net (code "22") (name "/RX_RY") (class "Default")
      (node (ref "R27") (pin "2") (pinfunction "2_2") (pintype "input"))
      (node (ref "U2") (pin "13") (pinfunction "PA3USART2_RXADC12_IN3TIM2_CH4_13") (pintype "input"))
    )
    (net (code "23") (name "/SCL") (class "Default")
      (node (ref "H1") (pin "2") (pinfunction "2_2") (pintype "input"))
      (node (ref "U2") (pin "4") (pinfunction "PC15-OSC32_OUT_4") (pintype "input"))
    )
    (net (code "24") (name "/SDA") (class "Default")
      (node (ref "H1") (pin "1") (pinfunction "1_1") (pintype "input"))
      (node (ref "U2") (pin "3") (pinfunction "PC14-OSC32_IN_3") (pintype "input"))
    )
    (net (code "25") (name "/SPI_CLK") (class "Default")
      (node (ref "R30") (pin "2") (pinfunction "2_2") (pintype "input"))
      (node (ref "U2") (pin "15") (pinfunction "PA5SPI1_SCKADC12_IN5_15") (pintype "input"))
      (node (ref "U3") (pin "6") (pinfunction "CLK_6") (pintype "input"))
    )
    (net (code "26") (name "/SPI_CS") (class "Default")
      (node (ref "R14") (pin "1") (pinfunction "1_1") (pintype "input"))
      (node (ref "U2") (pin "14") (pinfunction "PA4SPI1_NSSUSART2_CKADC12_IN4_14") (pintype "input"))
      (node (ref "U3") (pin "1") (pinfunction "CS#_1") (pintype "input"))
    )
    (net (code "27") (name "/SPI_MISO") (class "Default")
      (node (ref "U2") (pin "16") (pinfunction "PA6SPI1_MISOADC12_IN6TIM3_CH1_16") (pintype "input"))
      (node (ref "U3") (pin "2") (pinfunction "DO(IO1)_2") (pintype "input"))
    )
    (net (code "28") (name "/SPI_MOSI") (class "Default")
      (node (ref "U2") (pin "17") (pinfunction "PA7SPI1_MOSIADC12_IN7TIM3_CH2_17") (pintype "input"))
      (node (ref "U3") (pin "5") (pinfunction "DI(IO0)_5") (pintype "input"))
    )
    (net (code "29") (name "/SWIN") (class "Default")
      (node (ref "R13") (pin "2") (pinfunction "2_2") (pintype "input"))
      (node (ref "R7") (pin "1") (pinfunction "1_1") (pintype "input"))
      (node (ref "R9") (pin "1") (pinfunction "1_1") (pintype "input"))
      (node (ref "U2") (pin "22") (pinfunction "PB11I2C2_SDAUSART3_RX-_22") (pintype "input"))
      (node (ref "U2") (pin "45") (pinfunction "PB8TIM4_CH3_45") (pintype "input"))
    )
    (net (code "30") (name "/SWIN_DAP") (class "Default")
      (node (ref "H2") (pin "17") (pinfunction "17_17") (pintype "input"))
      (node (ref "R13") (pin "1") (pinfunction "1_1") (pintype "input"))
    )
    (net (code "31") (name "/SWIN_RST_DAP") (class "Default")
      (node (ref "H2") (pin "15") (pinfunction "15_15") (pintype "input"))
      (node (ref "R12") (pin "1") (pinfunction "1_1") (pintype "input"))
    )
    (net (code "32") (name "/S_IN") (class "Default")
      (node (ref "R9") (pin "2") (pinfunction "2_2") (pintype "input"))
      (node (ref "U2") (pin "21") (pinfunction "PB10I2C2_SCLUSART3_TX_21") (pintype "input"))
      (node (ref "U2") (pin "43") (pinfunction "PB7I2C1_SDATIM4_CH2_43") (pintype "input"))
      (node (ref "U2") (pin "46") (pinfunction "PB9TIM4_CH4_46") (pintype "input"))
    )
    (net (code "33") (name "/S_RST") (class "Default")
      (node (ref "R11") (pin "1") (pinfunction "1_1") (pintype "input"))
      (node (ref "R12") (pin "2") (pinfunction "2_2") (pintype "input"))
      (node (ref "U2") (pin "42") (pinfunction "PB6I2C1_SCLTIM4_CH1_42") (pintype "input"))
    )
    (net (code "34") (name "/S_RST_IN") (class "Default")
      (node (ref "R11") (pin "2") (pinfunction "2_2") (pintype "input"))
      (node (ref "U2") (pin "41") (pinfunction "PB5I2C1_SMBA_41") (pintype "input"))
    )
    (net (code "35") (name "/TCK") (class "Default")
      (node (ref "H2") (pin "10") (pinfunction "10_10") (pintype "input"))
      (node (ref "U2") (pin "37") (pinfunction "PA14JTCKSWCLK_37") (pintype "input"))
    )
    (net (code "36") (name "/TMS") (class "Default")
      (node (ref "H2") (pin "4") (pinfunction "4_4") (pintype "input"))
      (node (ref "U2") (pin "34") (pinfunction "PA13JTMSSWDIO_34") (pintype "input"))
    )
    (net (code "37") (name "/TXD") (class "Default")
      (node (ref "H2") (pin "14") (pinfunction "14_14") (pintype "input"))
      (node (ref "U2") (pin "30") (pinfunction "PA9USART1_TXTIM1_CH2_30") (pintype "input"))
    )
    (net (code "38") (name "/TX_DAP") (class "Default")
      (node (ref "H2") (pin "13") (pinfunction "13_13") (pintype "input"))
      (node (ref "LED2") (pin "2") (pinfunction "K_2") (pintype "input"))
      (node (ref "R26") (pin "1") (pinfunction "1_1") (pintype "input"))
    )
    (net (code "39") (name "/TX_RY") (class "Default")
      (node (ref "R26") (pin "2") (pinfunction "2_2") (pintype "input"))
      (node (ref "U2") (pin "12") (pinfunction "PA2USART2_TXADC12_IN2TIM2_CH3_12") (pintype "input"))
    )
    (net (code "40") (name "/USB+") (class "Default")
      (node (ref "Q1") (pin "3") (pinfunction "D_3") (pintype "input"))
      (node (ref "R4") (pin "1") (pinfunction "1_1") (pintype "input"))
      (node (ref "U2") (pin "33") (pinfunction "PA12USART1_RTSCAN_TXTIM1_ETRUSBDP_33") (pintype "input"))
    )
    (net (code "41") (name "/USB-") (class "Default")
      (node (ref "R5") (pin "1") (pinfunction "1_1") (pintype "input"))
      (node (ref "U2") (pin "32") (pinfunction "PA11USART1_CTSCAN_RXTIM1_CH4USBDM_32") (pintype "input"))
    )
    (net (code "42") (name "/USB_RENUM") (class "Default")
      (node (ref "R2") (pin "1") (pinfunction "1_1") (pintype "input"))
      (node (ref "R3") (pin "1") (pinfunction "1_1") (pintype "input"))
      (node (ref "U2") (pin "38") (pinfunction "PA15JTDI_38") (pintype "input"))
    )
    (net (code "43") (name "3V3") (class "Default")
      (node (ref "BUZZER1") (pin "1") (pinfunction "+_1") (pintype "input"))
      (node (ref "C3") (pin "1") (pinfunction "1_1") (pintype "input"))
      (node (ref "C4") (pin "2") (pinfunction "2_2") (pintype "input"))
      (node (ref "C8") (pin "2") (pinfunction "2_2") (pintype "input"))
      (node (ref "H1") (pin "3") (pinfunction "3_3") (pintype "input"))
      (node (ref "H2") (pin "1") (pinfunction "1_1") (pintype "input"))
      (node (ref "H2") (pin "18") (pinfunction "18_18") (pintype "input"))
      (node (ref "H2") (pin "2") (pinfunction "2_2") (pintype "input"))
      (node (ref "R1") (pin "2") (pinfunction "2_2") (pintype "input"))
      (node (ref "R10") (pin "2") (pinfunction "2_2") (pintype "input"))
      (node (ref "R14") (pin "2") (pinfunction "2_2") (pintype "input"))
      (node (ref "R16") (pin "2") (pinfunction "2_2") (pintype "input"))
      (node (ref "R18") (pin "2") (pinfunction "2_2") (pintype "input"))
      (node (ref "R19") (pin "2") (pinfunction "2_2") (pintype "input"))
      (node (ref "R2") (pin "2") (pinfunction "2_2") (pintype "input"))
      (node (ref "R21") (pin "2") (pinfunction "2_2") (pintype "input"))
      (node (ref "R22") (pin "2") (pinfunction "2_2") (pintype "input"))
      (node (ref "R23") (pin "2") (pinfunction "2_2") (pintype "input"))
      (node (ref "R24") (pin "2") (pinfunction "2_2") (pintype "input"))
      (node (ref "R7") (pin "2") (pinfunction "2_2") (pintype "input"))
      (node (ref "U1") (pin "2") (pinfunction "VOUT_2") (pintype "input"))
      (node (ref "U2") (pin "24") (pinfunction "VDD_1_24") (pintype "input"))
      (node (ref "U2") (pin "36") (pinfunction "VDD_2_36") (pintype "input"))
      (node (ref "U2") (pin "48") (pinfunction "VDD_3_48") (pintype "input"))
      (node (ref "U2") (pin "9") (pinfunction "VDD_A_9") (pintype "input"))
      (node (ref "U3") (pin "3") (pinfunction "WP#(IO2)_3") (pintype "input"))
      (node (ref "U3") (pin "7") (pinfunction "HOLD#(IO3)_7") (pintype "input"))
      (node (ref "U3") (pin "8") (pinfunction "VCC_8") (pintype "input"))
    )
    (net (code "44") (name "GND") (class "Default")
      (node (ref "C1") (pin "1") (pinfunction "1_1") (pintype "input"))
      (node (ref "C2") (pin "1") (pinfunction "1_1") (pintype "input"))
      (node (ref "C3") (pin "2") (pinfunction "2_2") (pintype "input"))
      (node (ref "C4") (pin "1") (pinfunction "1_1") (pintype "input"))
      (node (ref "C5") (pin "1") (pinfunction "1_1") (pintype "input"))
      (node (ref "C6") (pin "2") (pinfunction "2_2") (pintype "input"))
      (node (ref "C7") (pin "2") (pinfunction "2_2") (pintype "input"))
      (node (ref "C8") (pin "1") (pinfunction "1_1") (pintype "input"))
      (node (ref "H1") (pin "4") (pinfunction "4_4") (pintype "input"))
      (node (ref "H2") (pin "5") (pinfunction "5_5") (pintype "input"))
      (node (ref "H2") (pin "6") (pinfunction "6_6") (pintype "input"))
      (node (ref "LED1") (pin "2") (pinfunction "K_2") (pintype "input"))
      (node (ref "Q2") (pin "3") (pinfunction "D_3") (pintype "input"))
      (node (ref "R29") (pin "1") (pinfunction "1_1") (pintype "input"))
      (node (ref "R8") (pin "1") (pinfunction "1_1") (pintype "input"))
      (node (ref "SW1") (pin "2") (pinfunction "2_2") (pintype "input"))
      (node (ref "SW1") (pin "3") (pinfunction "3_3") (pintype "input"))
      (node (ref "SW1") (pin "4") (pinfunction "4_4") (pintype "input"))
      (node (ref "SW2") (pin "2") (pinfunction "2_2") (pintype "input"))
      (node (ref "SW2") (pin "3") (pinfunction "3_3") (pintype "input"))
      (node (ref "SW2") (pin "4") (pinfunction "4_4") (pintype "input"))
      (node (ref "SW3") (pin "2") (pinfunction "2_2") (pintype "input"))
      (node (ref "SW3") (pin "3") (pinfunction "3_3") (pintype "input"))
      (node (ref "SW3") (pin "4") (pinfunction "4_4") (pintype "input"))
      (node (ref "U1") (pin "1") (pinfunction "GND_1") (pintype "input"))
      (node (ref "U2") (pin "23") (pinfunction "VSS_1_23") (pintype "input"))
      (node (ref "U2") (pin "35") (pinfunction "VSS_2_35") (pintype "input"))
      (node (ref "U2") (pin "47") (pinfunction "VSS_3_47") (pintype "input"))
      (node (ref "U2") (pin "8") (pinfunction "VSS_A_8") (pintype "input"))
      (node (ref "U3") (pin "4") (pinfunction "GND_4") (pintype "input"))
      (node (ref "USB1") (pin "1") (pinfunction "SHELL_1") (pintype "input"))
      (node (ref "USB1") (pin "2") (pinfunction "SHELL_2") (pintype "input"))
      (node (ref "USB1") (pin "3") (pinfunction "SHELL_3") (pintype "input"))
      (node (ref "USB1") (pin "4") (pinfunction "SHELL_4") (pintype "input"))
      (node (ref "USB1") (pin "A1B12") (pinfunction "GND_A1B12") (pintype "input"))
      (node (ref "USB1") (pin "B1A12") (pinfunction "GND_B1A12") (pintype "input"))
    )
    (net (code "45") (name "Net-(BUZZER1--)") (class "Default")
      (node (ref "BUZZER1") (pin "2") (pinfunction "-_2") (pintype "input"))
      (node (ref "Q2") (pin "2") (pinfunction "S_2") (pintype "input"))
    )
    (net (code "46") (name "Net-(LED1-A)") (class "Default")
      (node (ref "LED1") (pin "1") (pinfunction "A_1") (pintype "input"))
      (node (ref "R6") (pin "2") (pinfunction "2_2") (pintype "input"))
    )
    (net (code "47") (name "Net-(LED2-A)") (class "Default")
      (node (ref "LED2") (pin "1") (pinfunction "A_1") (pintype "input"))
      (node (ref "R18") (pin "1") (pinfunction "1_1") (pintype "input"))
    )
    (net (code "48") (name "Net-(LED3-A)") (class "Default")
      (node (ref "LED3") (pin "1") (pinfunction "A_1") (pintype "input"))
      (node (ref "R19") (pin "1") (pinfunction "1_1") (pintype "input"))
    )
    (net (code "49") (name "Net-(Q1-G)") (class "Default")
      (node (ref "Q1") (pin "1") (pinfunction "G_1") (pintype "input"))
      (node (ref "R3") (pin "2") (pinfunction "2_2") (pintype "input"))
    )
    (net (code "50") (name "Net-(Q1-S)") (class "Default")
      (node (ref "Q1") (pin "2") (pinfunction "S_2") (pintype "input"))
      (node (ref "R1") (pin "1") (pinfunction "1_1") (pintype "input"))
    )
    (net (code "51") (name "Net-(Q2-G)") (class "Default")
      (node (ref "Q2") (pin "1") (pinfunction "G_1") (pintype "input"))
      (node (ref "R28") (pin "2") (pinfunction "2_2") (pintype "input"))
    )
    (net (code "52") (name "VCC") (class "Default")
      (node (ref "C1") (pin "2") (pinfunction "2_2") (pintype "input"))
      (node (ref "C2") (pin "2") (pinfunction "2_2") (pintype "input"))
      (node (ref "F1") (pin "2") (pinfunction "2_2") (pintype "input"))
      (node (ref "H2") (pin "19") (pinfunction "19_19") (pintype "input"))
      (node (ref "H2") (pin "20") (pinfunction "20_20") (pintype "input"))
      (node (ref "R6") (pin "1") (pinfunction "1_1") (pintype "input"))
      (node (ref "U1") (pin "3") (pinfunction "VIN_3") (pintype "input"))
    )
    (net (code "53") (name "unconnected-(U1-TAB-Pad4)") (class "Default")
      (node (ref "U1") (pin "4") (pinfunction "TAB_4") (pintype "input+no_connect"))
    )
    (net (code "54") (name "unconnected-(U2-PA1USART2_RTSADC12_IN1TIM2_CH2-Pad11)") (class "Default")
      (node (ref "U2") (pin "11") (pinfunction "PA1USART2_RTSADC12_IN1TIM2_CH2_11") (pintype "input+no_connect"))
    )
    (net (code "55") (name "unconnected-(U2-PB4NJTRST-Pad40)") (class "Default")
      (node (ref "U2") (pin "40") (pinfunction "PB4NJTRST_40") (pintype "input+no_connect"))
    )
    (net (code "56") (name "unconnected-(U2-PB15SPI2_MOSITIM1_CH3N-Pad28)") (class "Default")
      (node (ref "U2") (pin "28") (pinfunction "PB15SPI2_MOSITIM1_CH3N_28") (pintype "input+no_connect"))
    )
    (net (code "57") (name "unconnected-(U2-PC13-TAMPER-RTC-Pad2)") (class "Default")
      (node (ref "U2") (pin "2") (pinfunction "PC13-TAMPER-RTC_2") (pintype "input+no_connect"))
    )
    (net (code "58") (name "unconnected-(U2-VBAT-Pad1)") (class "Default")
      (node (ref "U2") (pin "1") (pinfunction "VBAT_1") (pintype "input+no_connect"))
    )
    (net (code "59") (name "unconnected-(USB1-CC1-PadA5)") (class "Default")
      (node (ref "USB1") (pin "A5") (pinfunction "CC1_A5") (pintype "input+no_connect"))
    )
    (net (code "60") (name "unconnected-(USB1-CC2-PadB5)") (class "Default")
      (node (ref "USB1") (pin "B5") (pinfunction "CC2_B5") (pintype "input+no_connect"))
    )
    (net (code "61") (name "unconnected-(USB1-SBU1-PadA8)") (class "Default")
      (node (ref "USB1") (pin "A8") (pinfunction "SBU1_A8") (pintype "input+no_connect"))
    )
    (net (code "62") (name "unconnected-(USB1-SBU2-PadB8)") (class "Default")
      (node (ref "USB1") (pin "B8") (pinfunction "SBU2_B8") (pintype "input+no_connect"))
    )
    (net (code "63") (name "unconnected-(X1-GND-Pad2)") (class "Default")
      (node (ref "X1") (pin "2") (pinfunction "GND_2") (pintype "input+no_connect"))
    )
    (net (code "64") (name "unconnected-(X1-GND-Pad4)") (class "Default")
      (node (ref "X1") (pin "4") (pinfunction "GND_4") (pintype "input+no_connect"))
    )
  )
)
